# 08_USB_OTG_POWER.net
KiCad netlist of a schematic drawn in Altium Designer
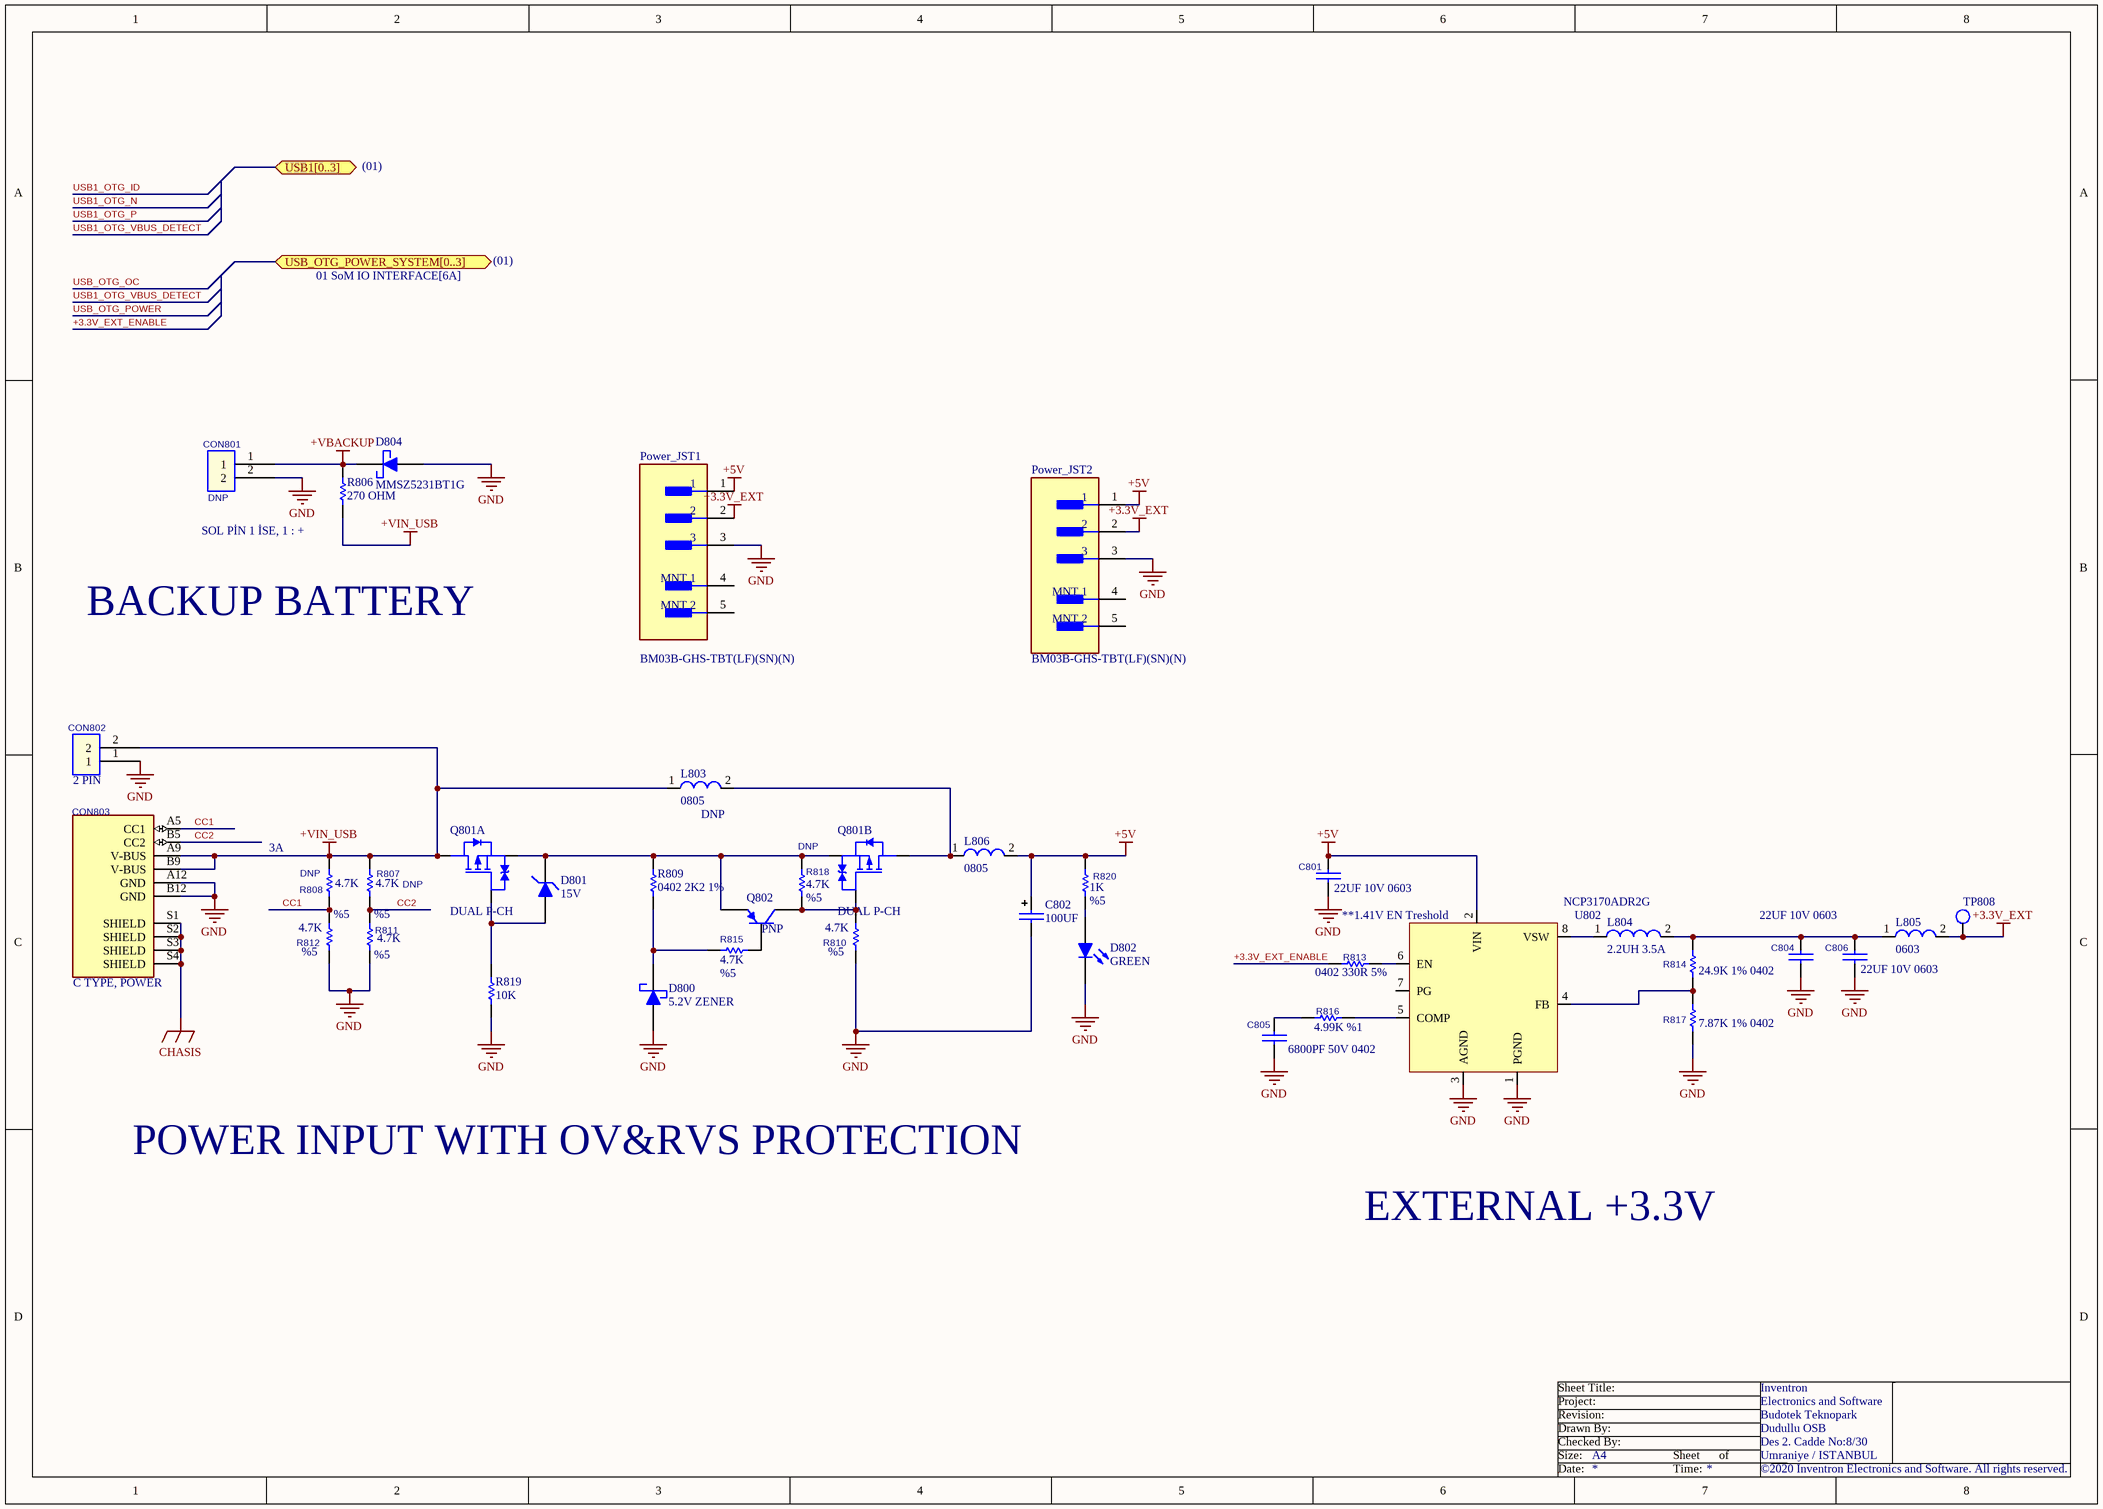
[diagram p0: 08 USB OTG & POWER.SchDoc]

(export (version "E")
  (design (tool "Eeschema 10.0.6"))
  (components
    (comp (ref "C801")
      (value "22UF 10V 0603")
      (footprint "0603_CC")
      (description "±20% 10V Ceramic Capacitor X5R 0603 (1608 Metric)")
      (fields (field (name "CREATED BY") "E.E") (field (name "CHECKED BY") "*"))
      (libsource (lib "ARETE_SCH") (part "CAP-C1608X5R1A226M080AC"))
    )
    (comp (ref "C802")
      (value "100UF")
      (footprint "UWR1A101MCL1GB")
      (description "CAP ALUM 100UF 20% 10V SMD")
      (fields (field (name "CREATED BY") "EE") (field (name "CHECKED BY") "*"))
      (libsource (lib "ARETE_V2_SCH") (part "CAP-UWR1A101MCL1GB"))
    )
    (comp (ref "C804")
      (value "22UF 10V 0603")
      (footprint "0603_CC")
      (description "±20% 10V Ceramic Capacitor X5R 0603 (1608 Metric)")
      (fields (field (name "CREATED BY") "E.E") (field (name "CHECKED BY") "*"))
      (libsource (lib "ARETE_SCH") (part "CAP-C1608X5R1A226M080AC"))
    )
    (comp (ref "C805")
      (value "6800PF 50V 0402")
      (footprint "0402_CC")
      (description "6800pF ±10% 50V Ceramic Capacitor X7R 0402 (1005 Metric)")
      (fields (field (name "CREATED BY") "E.E") (field (name "CHECKED BY") "*"))
      (libsource (lib "ARETE_SCH") (part "CAP-CL05B682KB5NNNC"))
    )
    (comp (ref "C806")
      (value "22UF 10V 0603")
      (footprint "0603_CC")
      (description "±20% 10V Ceramic Capacitor X5R 0603 (1608 Metric)")
      (fields (field (name "CREATED BY") "E.E") (field (name "CHECKED BY") "*"))
      (libsource (lib "ARETE_SCH") (part "CAP-C1608X5R1A226M080AC"))
    )
    (comp (ref "CON801")
      (value "CON-B2B-PH-K-S(LF)(SN)")
      (footprint "B2B-PH-K-S")
      (description "CONN HEADER VERT 2POS 2MM")
      (fields
        (field (name "ASSY_OPT") "DNP")
        (field (name "CREATED BY") "LA")
        (field (name "CHECKED BY") "*")
      )
      (libsource (lib "ARETE_L") (part "CON-B2B-PH-K-S(LF)(SN)"))
    )
    (comp (ref "CON802")
      (value "2 PIN")
      (footprint "640456-2")
      (description "CONN HEADER VERT 2POS 2.54MM")
      (fields (field (name "CREATED BY") "LA") (field (name "CHECKED BY") "*"))
      (libsource (lib "ARETE_L") (part "CON-640456-2"))
    )
    (comp (ref "CON803")
      (value "C TYPE, POWER")
      (footprint "CUI_UJC-HP-3-SMT-TR")
      (description "USB JACK, C TYPE, POWER ONLY, 6")
      (fields (field (name "CREATED BY") "E.E") (field (name "CHECKED BY") "*"))
      (libsource (lib "ARETE_SCH") (part "0-CON-UJC-HP-3-SMT-TR"))
    )
    (comp (ref "D800")
      (value "5.2V ZENER")
      (footprint "SOD-323")
      (description "DIODE ZENER 5.1V 320MW SOD323")
      (fields (field (name "CREATED BY") "EE") (field (name "CHECKED BY") "*"))
      (libsource (lib "ARETE_V2_SCH") (part "DIODE-PZU5.1B2A,115"))
    )
    (comp (ref "D801")
      (value "15V")
      (footprint "SOD-323")
      (description "DIODE ZENER 15V 400MW SOD323")
      (fields (field (name "CREATED BY") "LA") (field (name "CHECKED BY") "*"))
      (libsource (lib "ARETE_V2_SCH") (part "DIODE-PDZ15B,115"))
    )
    (comp (ref "D802")
      (value "GREEN")
      (footprint "0603_LED")
      (description "LED SMD 0603 SUPER GREEN")
      (fields (field (name "CREATED BY") "*") (field (name "CHECKED BY") "*"))
      (libsource (lib "ARETE_SCH") (part "LED-LTST-C190KRKT"))
    )
    (comp (ref "D804")
      (value "MMSZ5231BT1G")
      (footprint "SOD-123")
      (description "DIODE ZENER 5.1V 500MW SOD123")
      (fields (field (name "CREATED BY") "EE") (field (name "CHECKED BY") "*"))
      (libsource (lib "ARETE_SCH") (part "DIODE-MMSZ5231BT1G"))
    )
    (comp (ref "L803")
      (value "0805")
      (footprint "0805")
      (description "0OHM 0805")
      (fields
        (field (name "ASSY_OPT") "DNP")
        (field (name "CREATED BY") "EE")
        (field (name "CHECKED BY") "*")
      )
      (libsource (lib "ARETE_V2_SCH") (part "IND-FERRITE (RES 0 OHM) 0805"))
    )
    (comp (ref "L804")
      (value "2.2UH 3.5A")
      (footprint "IND-NRS5030T2R2NMGJ")
      (description "Shielded Wirewound Inductor 23mOhm Nonstandard")
      (fields (field (name "CREATED BY") "E.E") (field (name "CHECKED BY") "*"))
      (libsource (lib "ARETE_SCH") (part "IND-NRS5030T2R2NMGJ"))
    )
    (comp (ref "L805")
      (value "0603")
      (footprint "0603_RES")
      (description "0OHM 0603")
      (fields (field (name "CREATED BY") "EE") (field (name "CHECKED BY") "*"))
      (libsource (lib "ARETE_SCH") (part "IND-FERRITE (RES 0 OHM) 0603"))
    )
    (comp (ref "L806")
      (value "0805")
      (footprint "0805")
      (description "0OHM 0805")
      (fields (field (name "CREATED BY") "EE") (field (name "CHECKED BY") "*"))
      (libsource (lib "ARETE_V2_SCH") (part "IND-FERRITE (RES 0 OHM) 0805"))
    )
    (comp (ref "Power_JST1")
      (value "BM03B-GHS-TBT(LF)(SN)(N)")
      (footprint "FP-BM03B-GHS-TBT_LF_SN-MFG")
      (description "CONN HEADER SMD 3POS 1.25MM")
      (libsource (lib "Altium Content Vault") (part "38689d6f3df0f9b234c6ddcef280d85"))
    )
    (comp (ref "Power_JST2")
      (value "BM03B-GHS-TBT(LF)(SN)(N)")
      (footprint "FP-BM03B-GHS-TBT_LF_SN-MFG")
      (description "CONN HEADER SMD 3POS 1.25MM")
      (libsource (lib "Altium Content Vault") (part "38689d6f3df0f9b234c6ddcef280d85"))
    )
    (comp (ref "Q801")
      (value "DUAL P-CH")
      (footprint "SO-8 - DUAL MOS - NAMED")
      (description "MOSFET 2P-CH 30V 6A SO-8")
      (fields (field (name "CREATED BY") "*") (field (name "CHECKED BY") "*"))
      (libsource (lib "ARETE_V2_SCH") (part "MOS-P-DMP3028LSD-13"))
    )
    (comp (ref "Q802")
      (value "PNP")
      (footprint "SOT23")
      (description "TRANS PNP 65V 0.1A SOT-23")
      (fields (field (name "CREATED BY") "LA") (field (name "CHECKED BY") "*"))
      (libsource (lib "ARETE_V2_SCH") (part "TRANSISTOR-BC856"))
    )
    (comp (ref "R806")
      (value "270 OHM")
      (footprint "0603_RES")
      (description "RES SMD 270 OHM 5% 1/10W 0603")
      (fields (field (name "CREATED BY") "EE") (field (name "CHECKED BY") "*"))
      (libsource (lib "ARETE_SCH") (part "RES-RC0603JR-07270RL"))
    )
    (comp (ref "R807")
      (value "4.7K")
      (footprint "0402_RES")
      (description "RES 4.7K OHM 5% 1/16W 0402")
      (fields
        (field (name "ASSY_OPT") "DNP")
        (field (name "TOLERANCE") "%5")
        (field (name "CREATED BY") "LA")
        (field (name "CHECKED BY") "*")
      )
      (libsource (lib "ARETE_SCH") (part "RES-4.7K"))
    )
    (comp (ref "R808")
      (value "4.7K")
      (footprint "0402_RES")
      (description "RES 4.7K OHM 5% 1/16W 0402")
      (fields
        (field (name "ASSY_OPT") "DNP")
        (field (name "TOLERANCE") "%5")
        (field (name "CREATED BY") "LA")
        (field (name "CHECKED BY") "*")
      )
      (libsource (lib "ARETE_SCH") (part "RES-4.7K"))
    )
    (comp (ref "R809")
      (value "0402 2K2 1%")
      (footprint "0402_RES")
      (fields (field (name "CREATED BY") "E.E") (field (name "CHECKED BY") "*"))
      (libsource (lib "ARETE_V2_SCH") (part "RES-CRGCQ0402F2K2"))
    )
    (comp (ref "R810")
      (value "4.7K")
      (footprint "0402_RES")
      (description "RES 4.7K OHM 5% 1/16W 0402")
      (fields
        (field (name "TOLERANCE") "%5")
        (field (name "CREATED BY") "LA")
        (field (name "CHECKED BY") "*")
      )
      (libsource (lib "ARETE_SCH") (part "RES-4.7K"))
    )
    (comp (ref "R811")
      (value "4.7K")
      (footprint "0402_RES")
      (description "RES 4.7K OHM 5% 1/16W 0402")
      (fields
        (field (name "TOLERANCE") "%5")
        (field (name "CREATED BY") "LA")
        (field (name "CHECKED BY") "*")
      )
      (libsource (lib "ARETE_SCH") (part "RES-4.7K"))
    )
    (comp (ref "R812")
      (value "4.7K")
      (footprint "0402_RES")
      (description "RES 4.7K OHM 5% 1/16W 0402")
      (fields
        (field (name "TOLERANCE") "%5")
        (field (name "CREATED BY") "LA")
        (field (name "CHECKED BY") "*")
      )
      (libsource (lib "ARETE_SCH") (part "RES-4.7K"))
    )
    (comp (ref "R813")
      (value "0402 330R 5%")
      (footprint "0402_RES")
      (fields
        (field (name "TOLERANCE") "%5")
        (field (name "CREATED BY") "E.E")
        (field (name "CHECKED BY") "*")
      )
      (libsource (lib "ARETE_SCH") (part "RES-CRGCQ0402J330R"))
    )
    (comp (ref "R814")
      (value "24.9K 1% 0402")
      (footprint "0402_RES")
      (description "24.9 ±1% 0.063W, 1/16W Chip Resistor 0402 (1005 Metric) - Thick Film")
      (fields (field (name "CREATED BY") "E.E") (field (name "CHECKED BY") "*"))
      (libsource (lib "ARETE_SCH") (part "RES-RC0402FR-0724K9L"))
    )
    (comp (ref "R815")
      (value "4.7K")
      (footprint "0402_RES")
      (description "RES 4.7K OHM 5% 1/16W 0402")
      (fields
        (field (name "TOLERANCE") "%5")
        (field (name "CREATED BY") "LA")
        (field (name "CHECKED BY") "*")
      )
      (libsource (lib "ARETE_SCH") (part "RES-4.7K"))
    )
    (comp (ref "R816")
      (value "4.99K %1")
      (footprint "0603_RES")
      (description "RES 4.99K OHM %1 1/10W 0603")
      (fields (field (name "CREATED BY") "LA") (field (name "CHECKED BY") "*"))
      (libsource (lib "ARETE_SCH") (part "RES-RC0603FR-074K99L"))
    )
    (comp (ref "R817")
      (value "7.87K 1% 0402")
      (footprint "0402_RES")
      (description "7.87 kOhms ±1% 0.063W, 1/16W Chip Resistor 0402 (1005 Metric) Automotive AEC-Q200 Thick Film")
      (fields (field (name "CREATED BY") "EE") (field (name "CHECKED BY") "*"))
      (libsource (lib "ARETE_SCH") (part "RES-CRCW04027K87FKED"))
    )
    (comp (ref "R818")
      (value "4.7K")
      (footprint "0402_RES")
      (description "RES 4.7K OHM 5% 1/16W 0402")
      (fields
        (field (name "ASSY_OPT") "DNP")
        (field (name "TOLERANCE") "%5")
        (field (name "CREATED BY") "LA")
        (field (name "CHECKED BY") "*")
      )
      (libsource (lib "ARETE_SCH") (part "RES-4.7K"))
    )
    (comp (ref "R819")
      (value "10K")
      (footprint "0805")
      (description "RES SMD 10K 5% 0805")
      (fields (field (name "CREATED BY") "*") (field (name "CHECKED BY") "*"))
      (libsource (lib "ARETE_V2_SCH") (part "RES-0805S8J0103TDE"))
    )
    (comp (ref "R820")
      (value "1K")
      (footprint "0402_RES")
      (description "RES 1K OHM 5% 1/16W 0402")
      (fields
        (field (name "TOLERANCE") "%5")
        (field (name "CREATED BY") "LA")
        (field (name "CHECKED BY") "*")
      )
      (libsource (lib "ARETE_SCH") (part "RES-RMCF0402JT1K00"))
    )
    (comp (ref "TP808")
      (value "TEST POINT 35")
      (footprint "testpoint_35mil")
      (libsource (lib "ARETE_SCH") (part "TEST POINT 35"))
    )
    (comp (ref "U802")
      (value "NCP3170ADR2G")
      (footprint "IC-NCP3170ADR2G")
      (description "Buck Regulator, Switching, PWM, 3.0 A")
      (fields (field (name "CREATED BY") "E.E") (field (name "CHECKED BY") "*"))
      (libsource (lib "ARETE_SCH") (part "IC-NCP3170ADR2G"))
    )
  )
  (nets
    (net (code "9") (name "+3.3V_EXT") (class "Default")
      (node (ref "L805") (pin "2") (pinfunction "2_2") (pintype "passive"))
      (node (ref "Power_JST1") (pin "2") (pinfunction "2_2") (pintype "passive"))
      (node (ref "Power_JST2") (pin "2") (pinfunction "2_2") (pintype "passive"))
      (node (ref "TP808") (pin "1") (pinfunction "1_1") (pintype "passive"))
    )
    (net (code "10") (name "+5V") (class "Default")
      (node (ref "C801") (pin "1") (pinfunction "1_1") (pintype "passive"))
      (node (ref "C802") (pin "1") (pinfunction "1_1") (pintype "passive"))
      (node (ref "L806") (pin "2") (pinfunction "2_2") (pintype "passive"))
      (node (ref "Power_JST1") (pin "1") (pinfunction "1_1") (pintype "passive"))
      (node (ref "Power_JST2") (pin "1") (pinfunction "1_1") (pintype "passive"))
      (node (ref "R820") (pin "1") (pinfunction "1_1") (pintype "passive"))
      (node (ref "U802") (pin "2") (pinfunction "VIN_2") (pintype "passive"))
    )
    (net (code "11") (name "+VBACKUP") (class "Default")
      (node (ref "CON801") (pin "1") (pinfunction "1_1") (pintype "passive"))
      (node (ref "D804") (pin "K") (pinfunction "K_K") (pintype "passive"))
      (node (ref "R806") (pin "1") (pinfunction "1_1") (pintype "passive"))
    )
    (net (code "12") (name "+VIN_USB") (class "Default")
      (node (ref "CON802") (pin "2") (pinfunction "2_2") (pintype "passive"))
      (node (ref "CON803") (pin "A9") (pinfunction "V-BUS_A9") (pintype "power_in"))
      (node (ref "CON803") (pin "B9") (pinfunction "V-BUS_B9") (pintype "power_in"))
      (node (ref "L803") (pin "1") (pinfunction "1_1") (pintype "passive"))
      (node (ref "Q801") (pin "D1") (pinfunction "D1_D1") (pintype "passive"))
      (node (ref "R806") (pin "2") (pinfunction "2_2") (pintype "passive"))
      (node (ref "R807") (pin "1") (pinfunction "1_1") (pintype "passive"))
      (node (ref "R808") (pin "1") (pinfunction "1_1") (pintype "passive"))
    )
    (net (code "13") (name "/+3.3V_EXT_ENABLE") (class "Default")
      (node (ref "R813") (pin "1") (pinfunction "1_1") (pintype "passive"))
    )
    (net (code "14") (name "/CC1") (class "Default")
      (node (ref "CON803") (pin "A5") (pinfunction "CC1_A5") (pintype "bidirectional"))
      (node (ref "R808") (pin "2") (pinfunction "2_2") (pintype "passive"))
      (node (ref "R812") (pin "1") (pinfunction "1_1") (pintype "passive"))
    )
    (net (code "15") (name "/CC2") (class "Default")
      (node (ref "CON803") (pin "B5") (pinfunction "CC2_B5") (pintype "bidirectional"))
      (node (ref "R807") (pin "2") (pinfunction "2_2") (pintype "passive"))
      (node (ref "R811") (pin "1") (pinfunction "1_1") (pintype "passive"))
    )
    (net (code "24") (name "CHASIS") (class "Default")
      (node (ref "CON803") (pin "S1") (pinfunction "SHIELD_S1") (pintype "passive"))
      (node (ref "CON803") (pin "S2") (pinfunction "SHIELD_S2") (pintype "passive"))
      (node (ref "CON803") (pin "S3") (pinfunction "SHIELD_S3") (pintype "passive"))
      (node (ref "CON803") (pin "S4") (pinfunction "SHIELD_S4") (pintype "passive"))
    )
    (net (code "25") (name "GND") (class "Default")
      (node (ref "C801") (pin "2") (pinfunction "2_2") (pintype "passive"))
      (node (ref "C802") (pin "2") (pinfunction "2_2") (pintype "passive"))
      (node (ref "C804") (pin "2") (pinfunction "2_2") (pintype "passive"))
      (node (ref "C805") (pin "2") (pinfunction "2_2") (pintype "passive"))
      (node (ref "C806") (pin "2") (pinfunction "2_2") (pintype "passive"))
      (node (ref "CON801") (pin "2") (pinfunction "2_2") (pintype "passive"))
      (node (ref "CON802") (pin "1") (pinfunction "1_1") (pintype "passive"))
      (node (ref "CON803") (pin "A12") (pinfunction "GND_A12") (pintype "power_in"))
      (node (ref "CON803") (pin "B12") (pinfunction "GND_B12") (pintype "power_in"))
      (node (ref "D800") (pin "A") (pinfunction "A_A") (pintype "passive"))
      (node (ref "D802") (pin "2") (pinfunction "K_2") (pintype "passive"))
      (node (ref "D804") (pin "A") (pinfunction "A_A") (pintype "passive"))
      (node (ref "Power_JST1") (pin "3") (pinfunction "3_3") (pintype "passive"))
      (node (ref "Power_JST2") (pin "3") (pinfunction "3_3") (pintype "passive"))
      (node (ref "R810") (pin "2") (pinfunction "2_2") (pintype "passive"))
      (node (ref "R811") (pin "2") (pinfunction "2_2") (pintype "passive"))
      (node (ref "R812") (pin "2") (pinfunction "2_2") (pintype "passive"))
      (node (ref "R817") (pin "1") (pinfunction "1_1") (pintype "passive"))
      (node (ref "R819") (pin "1") (pinfunction "1_1") (pintype "passive"))
      (node (ref "U802") (pin "1") (pinfunction "PGND_1") (pintype "passive"))
      (node (ref "U802") (pin "3") (pinfunction "AGND_3") (pintype "passive"))
    )
    (net (code "26") (name "Net-(C804-Pad1)") (class "Default")
      (node (ref "C804") (pin "1") (pinfunction "1_1") (pintype "passive"))
      (node (ref "C806") (pin "1") (pinfunction "1_1") (pintype "passive"))
      (node (ref "L804") (pin "2") (pinfunction "2_2") (pintype "passive"))
      (node (ref "L805") (pin "1") (pinfunction "1_1") (pintype "passive"))
      (node (ref "R814") (pin "2") (pinfunction "2_2") (pintype "passive"))
    )
    (net (code "27") (name "Net-(C805-Pad1)") (class "Default")
      (node (ref "C805") (pin "1") (pinfunction "1_1") (pintype "passive"))
      (node (ref "R816") (pin "1") (pinfunction "1_1") (pintype "passive"))
    )
    (net (code "28") (name "Net-(D800-PadK)") (class "Default")
      (node (ref "D800") (pin "K") (pinfunction "K_K") (pintype "passive"))
      (node (ref "R809") (pin "1") (pinfunction "1_1") (pintype "passive"))
      (node (ref "R815") (pin "1") (pinfunction "1_1") (pintype "passive"))
    )
    (net (code "29") (name "Net-(D801-PadA)") (class "Default")
      (node (ref "D801") (pin "A") (pinfunction "A_A") (pintype "passive"))
      (node (ref "Q801") (pin "G1") (pinfunction "G1_G1") (pintype "passive"))
      (node (ref "R819") (pin "2") (pinfunction "2_2") (pintype "passive"))
    )
    (net (code "30") (name "Net-(D802-A)") (class "Default")
      (node (ref "D802") (pin "1") (pinfunction "A_1") (pintype "passive"))
      (node (ref "R820") (pin "2") (pinfunction "2_2") (pintype "passive"))
    )
    (net (code "31") (name "Net-(L803-Pad2)") (class "Default")
      (node (ref "L803") (pin "2") (pinfunction "2_2") (pintype "passive"))
      (node (ref "L806") (pin "1") (pinfunction "1_1") (pintype "passive"))
      (node (ref "Q801") (pin "D2") (pinfunction "D2_D2") (pintype "passive"))
    )
    (net (code "32") (name "Net-(Q802-B)") (class "Default")
      (node (ref "Q802") (pin "1") (pinfunction "B_1") (pintype "passive"))
      (node (ref "R815") (pin "2") (pinfunction "2_2") (pintype "passive"))
    )
    (net (code "33") (name "Net-(Q802-C)") (class "Default")
      (node (ref "Q801") (pin "G2") (pinfunction "G2_G2") (pintype "passive"))
      (node (ref "Q802") (pin "3") (pinfunction "C_3") (pintype "passive"))
      (node (ref "R810") (pin "1") (pinfunction "1_1") (pintype "passive"))
      (node (ref "R818") (pin "1") (pinfunction "1_1") (pintype "passive"))
    )
    (net (code "34") (name "Net-(Q802-E)") (class "Default")
      (node (ref "D801") (pin "K") (pinfunction "K_K") (pintype "passive"))
      (node (ref "Q801") (pin "S1") (pinfunction "S1_S1") (pintype "passive"))
      (node (ref "Q801") (pin "S2") (pinfunction "S2_S2") (pintype "passive"))
      (node (ref "Q802") (pin "2") (pinfunction "E_2") (pintype "passive"))
      (node (ref "R809") (pin "2") (pinfunction "2_2") (pintype "passive"))
      (node (ref "R818") (pin "2") (pinfunction "2_2") (pintype "passive"))
    )
    (net (code "35") (name "Net-(U802-COMP)") (class "Default")
      (node (ref "R816") (pin "2") (pinfunction "2_2") (pintype "passive"))
      (node (ref "U802") (pin "5") (pinfunction "COMP_5") (pintype "passive"))
    )
    (net (code "36") (name "Net-(U802-EN)") (class "Default")
      (node (ref "R813") (pin "2") (pinfunction "2_2") (pintype "passive"))
      (node (ref "U802") (pin "6") (pinfunction "EN_6") (pintype "passive"))
    )
    (net (code "37") (name "Net-(U802-FB)") (class "Default")
      (node (ref "R814") (pin "1") (pinfunction "1_1") (pintype "passive"))
      (node (ref "R817") (pin "2") (pinfunction "2_2") (pintype "passive"))
      (node (ref "U802") (pin "4") (pinfunction "FB_4") (pintype "passive"))
    )
    (net (code "38") (name "Net-(U802-VSW)") (class "Default")
      (node (ref "L804") (pin "1") (pinfunction "1_1") (pintype "passive"))
      (node (ref "U802") (pin "8") (pinfunction "VSW_8") (pintype "passive"))
    )
    (net (code "39") (name "unconnected-(Power_JST1-MNT_1-Pad4)") (class "Default")
      (node (ref "Power_JST1") (pin "4") (pinfunction "MNT_1_4") (pintype "passive"))
    )
    (net (code "40") (name "unconnected-(Power_JST1-MNT_2-Pad5)") (class "Default")
      (node (ref "Power_JST1") (pin "5") (pinfunction "MNT_2_5") (pintype "passive"))
    )
    (net (code "41") (name "unconnected-(Power_JST2-MNT_1-Pad4)") (class "Default")
      (node (ref "Power_JST2") (pin "4") (pinfunction "MNT_1_4") (pintype "passive"))
    )
    (net (code "42") (name "unconnected-(Power_JST2-MNT_2-Pad5)") (class "Default")
      (node (ref "Power_JST2") (pin "5") (pinfunction "MNT_2_5") (pintype "passive"))
    )
    (net (code "43") (name "unconnected-(U802-PG-Pad7)") (class "Default")
      (node (ref "U802") (pin "7") (pinfunction "PG_7") (pintype "passive"))
    )
  )
)
